# waterius-factory-3_0.net
KiCad netlist of a schematic drawn in EAGLE
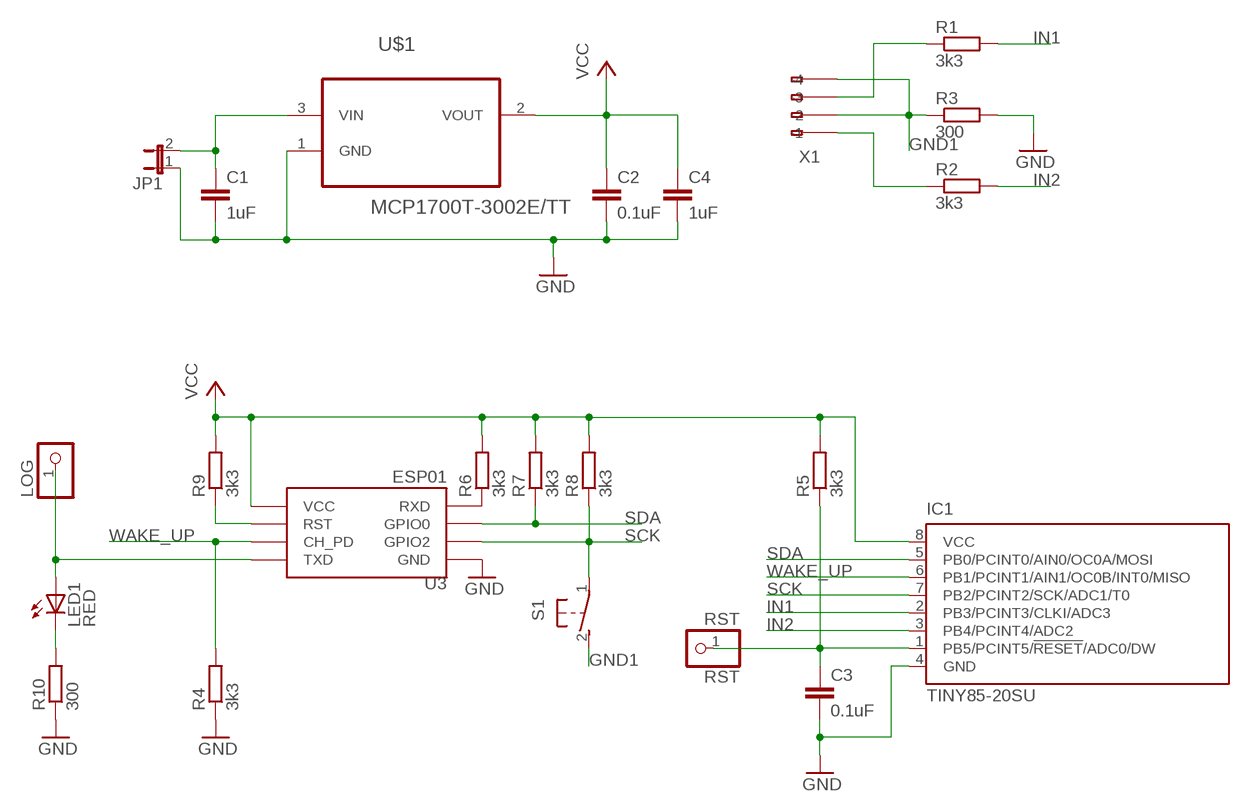
[diagram p0: schematic, sheet 1]

(export (version "E")
  (design (tool "Eeschema 10.0.6"))
  (components
    (comp (ref "C1")
      (value "1uF")
      (footprint "eagle-import:C0805")
      (libsource (lib "eagle-import") (part "C-EUC0805"))
    )
    (comp (ref "C2")
      (value "0.1uF")
      (footprint "eagle-import:C0805")
      (libsource (lib "eagle-import") (part "C-EUC0805"))
    )
    (comp (ref "C3")
      (value "0.1uF")
      (footprint "eagle-import:C0805")
      (libsource (lib "eagle-import") (part "C-EUC0805"))
    )
    (comp (ref "C4")
      (value "1uF")
      (footprint "eagle-import:C0805")
      (libsource (lib "eagle-import") (part "C-EUC0805"))
    )
    (comp (ref "IC1")
      (value "TINY85-20SU")
      (footprint "eagle-import:8S2")
      (fields (field (name "MPN") "ATTINY13-20SU"))
      (libsource (lib "eagle-import") (part "TINY13SU-20"))
    )
    (comp (ref "JP1")
      (value "JP1E")
      (footprint "eagle-import:JP1")
      (libsource (lib "eagle-import") (part "JP1E"))
    )
    (comp (ref "LED1")
      (value "RED")
      (footprint "eagle-import:LED3MM")
      (libsource (lib "eagle-import") (part "LED3MM"))
    )
    (comp (ref "LOG")
      (value "PINHD-1X1")
      (footprint "eagle-import:1X01")
      (libsource (lib "eagle-import") (part "PINHD-1X1"))
    )
    (comp (ref "R1")
      (value "3k3")
      (footprint "eagle-import:R0805")
      (libsource (lib "eagle-import") (part "R-EU_R0805"))
    )
    (comp (ref "R2")
      (value "3k3")
      (footprint "eagle-import:R0805")
      (libsource (lib "eagle-import") (part "R-EU_R0805"))
    )
    (comp (ref "R3")
      (value "300")
      (footprint "eagle-import:R0805")
      (libsource (lib "eagle-import") (part "R-EU_R0805"))
    )
    (comp (ref "R4")
      (value "3k3")
      (footprint "eagle-import:R0805")
      (libsource (lib "eagle-import") (part "R-EU_R0805"))
    )
    (comp (ref "R5")
      (value "3k3")
      (footprint "eagle-import:R0805")
      (libsource (lib "eagle-import") (part "R-EU_R0805"))
    )
    (comp (ref "R6")
      (value "3k3")
      (footprint "eagle-import:R0805")
      (libsource (lib "eagle-import") (part "R-EU_R0805"))
    )
    (comp (ref "R7")
      (value "3k3")
      (footprint "eagle-import:R0805")
      (libsource (lib "eagle-import") (part "R-EU_R0805"))
    )
    (comp (ref "R8")
      (value "3k3")
      (footprint "eagle-import:R0805")
      (libsource (lib "eagle-import") (part "R-EU_R0805"))
    )
    (comp (ref "R9")
      (value "3k3")
      (footprint "eagle-import:R0805")
      (libsource (lib "eagle-import") (part "R-EU_R0805"))
    )
    (comp (ref "R10")
      (value "300")
      (footprint "eagle-import:R0805")
      (libsource (lib "eagle-import") (part "R-EU_R0805"))
    )
    (comp (ref "RST")
      (value "RST")
      (footprint "eagle-import:1X01")
      (libsource (lib "eagle-import") (part "PINHD-1X1"))
    )
    (comp (ref "S1")
      (value "31-XX")
      (footprint "eagle-import:B3F-31XX")
      (fields (field (name "MPN") "B3F-3100"))
      (libsource (lib "eagle-import") (part "31-XX"))
    )
    (comp (ref "U$1")
      (value "MCP1700T-3002E/TT")
      (footprint "eagle-import:SOT95P237X112-3N")
      (fields (field (name "MF") "Microchip"))
      (libsource (lib "eagle-import") (part "MCP1700T-3002E/TT"))
    )
    (comp (ref "U3")
      (value "ESP01")
      (footprint "eagle-import:ESP01")
      (libsource (lib "eagle-import") (part "ESP01"))
    )
    (comp (ref "X1")
      (value "233-104")
      (footprint "eagle-import:233-104")
      (libsource (lib "eagle-import") (part "233-104"))
    )
  )
  (nets
    (net (code "1") (name "/GND1") (class "Default")
      (node (ref "R3") (pin "1") (pinfunction "1_1") (pintype "passive"))
      (node (ref "S1") (pin "2") (pinfunction "S_2") (pintype "passive"))
      (node (ref "X1") (pin "A2") (pinfunction "-2_A2") (pintype "passive"))
      (node (ref "X1") (pin "A4") (pinfunction "-4_A4") (pintype "passive"))
    )
    (net (code "2") (name "/IN1") (class "Default")
      (node (ref "IC1") (pin "2") (pinfunction "PB3/PCINT3/CLKI/ADC3_2") (pintype "bidirectional"))
      (node (ref "R1") (pin "2") (pinfunction "2_2") (pintype "passive"))
    )
    (net (code "3") (name "/IN2") (class "Default")
      (node (ref "IC1") (pin "3") (pinfunction "PB4/PCINT4/ADC2_3") (pintype "bidirectional"))
      (node (ref "R2") (pin "2") (pinfunction "2_2") (pintype "passive"))
    )
    (net (code "4") (name "/SCK") (class "Default")
      (node (ref "IC1") (pin "7") (pinfunction "PB2/PCINT2/SCK/ADC1/T0_7") (pintype "bidirectional"))
      (node (ref "R8") (pin "1") (pinfunction "1_1") (pintype "passive"))
      (node (ref "S1") (pin "1") (pinfunction "P_1") (pintype "passive"))
      (node (ref "U3") (pin "GPIO2") (pinfunction "GPIO2_GPIO2") (pintype "bidirectional"))
    )
    (net (code "5") (name "/SDA") (class "Default")
      (node (ref "IC1") (pin "5") (pinfunction "PB0/PCINT0/AIN0/OC0A/MOSI_5") (pintype "bidirectional"))
      (node (ref "R7") (pin "1") (pinfunction "1_1") (pintype "passive"))
      (node (ref "U3") (pin "GPIO0") (pinfunction "GPIO0_GPIO0") (pintype "bidirectional"))
    )
    (net (code "6") (name "/WAKE_UP") (class "Default")
      (node (ref "IC1") (pin "6") (pinfunction "PB1/PCINT1/AIN1/OC0B/INT0/MISO_6") (pintype "bidirectional"))
      (node (ref "R4") (pin "2") (pinfunction "2_2") (pintype "passive"))
      (node (ref "U3") (pin "CH_PD") (pinfunction "CH_PD_CH_PD") (pintype "bidirectional"))
    )
    (net (code "7") (name "GND") (class "Default")
      (node (ref "C1") (pin "2") (pinfunction "2_2") (pintype "passive"))
      (node (ref "C2") (pin "2") (pinfunction "2_2") (pintype "passive"))
      (node (ref "C3") (pin "2") (pinfunction "2_2") (pintype "passive"))
      (node (ref "C4") (pin "2") (pinfunction "2_2") (pintype "passive"))
      (node (ref "IC1") (pin "4") (pinfunction "GND_4") (pintype "power_in"))
      (node (ref "JP1") (pin "1") (pinfunction "1_1") (pintype "passive"))
      (node (ref "R10") (pin "1") (pinfunction "1_1") (pintype "passive"))
      (node (ref "R3") (pin "2") (pinfunction "2_2") (pintype "passive"))
      (node (ref "R4") (pin "1") (pinfunction "1_1") (pintype "passive"))
      (node (ref "U$1") (pin "1") (pinfunction "GND_1") (pintype "passive"))
      (node (ref "U3") (pin "GND") (pinfunction "GND_GND") (pintype "bidirectional"))
    )
    (net (code "8") (name "Net-(IC1-PB5{slash}PCINT5{slash}~{RESET}{slash}ADC0{slash}DW)") (class "Default")
      (node (ref "C3") (pin "1") (pinfunction "1_1") (pintype "passive"))
      (node (ref "IC1") (pin "1") (pinfunction "PB5/PCINT5/~{RESET}/ADC0/DW_1") (pintype "bidirectional"))
      (node (ref "R5") (pin "1") (pinfunction "1_1") (pintype "passive"))
      (node (ref "RST") (pin "1") (pinfunction "1_1") (pintype "passive"))
    )
    (net (code "9") (name "Net-(LED1-C)") (class "Default")
      (node (ref "LED1") (pin "K") (pinfunction "C_K") (pintype "passive"))
      (node (ref "R10") (pin "2") (pinfunction "2_2") (pintype "passive"))
    )
    (net (code "10") (name "Net-(R9-Pad1)") (class "Default")
      (node (ref "R9") (pin "1") (pinfunction "1_1") (pintype "passive"))
      (node (ref "U3") (pin "RST") (pinfunction "RST_RST") (pintype "bidirectional"))
    )
    (net (code "11") (name "Net-(U$1-VIN)") (class "Default")
      (node (ref "C1") (pin "1") (pinfunction "1_1") (pintype "passive"))
      (node (ref "JP1") (pin "2") (pinfunction "2_2") (pintype "passive"))
      (node (ref "U$1") (pin "3") (pinfunction "VIN_3") (pintype "input"))
    )
    (net (code "12") (name "Net-(U3-RXD)") (class "Default")
      (node (ref "R6") (pin "1") (pinfunction "1_1") (pintype "passive"))
      (node (ref "U3") (pin "RX") (pinfunction "RXD_RX") (pintype "bidirectional"))
    )
    (net (code "13") (name "Net-(U3-TXD)") (class "Default")
      (node (ref "LED1") (pin "A") (pinfunction "A_A") (pintype "passive"))
      (node (ref "LOG") (pin "1") (pinfunction "1_1") (pintype "passive"))
      (node (ref "U3") (pin "TX") (pinfunction "TXD_TX") (pintype "bidirectional"))
    )
    (net (code "14") (name "Net-(X1--1)") (class "Default")
      (node (ref "R2") (pin "1") (pinfunction "1_1") (pintype "passive"))
      (node (ref "X1") (pin "A1") (pinfunction "-1_A1") (pintype "passive"))
    )
    (net (code "15") (name "Net-(X1--3)") (class "Default")
      (node (ref "R1") (pin "1") (pinfunction "1_1") (pintype "passive"))
      (node (ref "X1") (pin "A3") (pinfunction "-3_A3") (pintype "passive"))
    )
    (net (code "16") (name "VCC") (class "Default")
      (node (ref "C2") (pin "1") (pinfunction "1_1") (pintype "passive"))
      (node (ref "C4") (pin "1") (pinfunction "1_1") (pintype "passive"))
      (node (ref "IC1") (pin "8") (pinfunction "VCC_8") (pintype "power_in"))
      (node (ref "R5") (pin "2") (pinfunction "2_2") (pintype "passive"))
      (node (ref "R6") (pin "2") (pinfunction "2_2") (pintype "passive"))
      (node (ref "R7") (pin "2") (pinfunction "2_2") (pintype "passive"))
      (node (ref "R8") (pin "2") (pinfunction "2_2") (pintype "passive"))
      (node (ref "R9") (pin "2") (pinfunction "2_2") (pintype "passive"))
      (node (ref "U$1") (pin "2") (pinfunction "VOUT_2") (pintype "output"))
      (node (ref "U3") (pin "VCC") (pinfunction "VCC_VCC") (pintype "bidirectional"))
    )
    (net (code "17") (name "unconnected-(X1-B-1-PadB1)") (class "Default")
      (node (ref "X1") (pin "B1") (pinfunction "B-1_B1") (pintype "passive"))
    )
    (net (code "18") (name "unconnected-(X1-B-2-PadB2)") (class "Default")
      (node (ref "X1") (pin "B2") (pinfunction "B-2_B2") (pintype "passive"))
    )
    (net (code "19") (name "unconnected-(X1-B-3-PadB3)") (class "Default")
      (node (ref "X1") (pin "B3") (pinfunction "B-3_B3") (pintype "passive"))
    )
    (net (code "20") (name "unconnected-(X1-B-4-PadB4)") (class "Default")
      (node (ref "X1") (pin "B4") (pinfunction "B-4_B4") (pintype "passive"))
    )
  )
)
